# HackadayPin.net
KiCad netlist of a schematic drawn in EAGLE
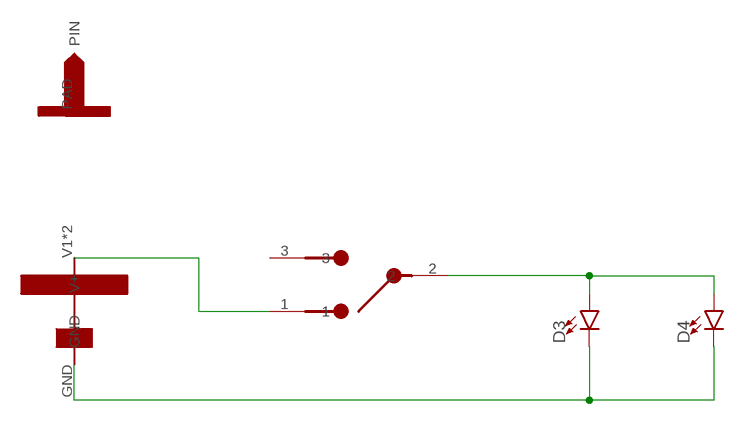
[diagram p0: schematic, sheet 1]

(export (version "E")
  (design (tool "Eeschema 10.0.6"))
  (components
    (comp (ref "D3")
      (value "LED5MM")
      (footprint "eagle-import:LED_5MM")
      (libsource (lib "eagle-import") (part "LED5MM"))
    )
    (comp (ref "D4")
      (value "LED5MM")
      (footprint "eagle-import:LED_5MM")
      (libsource (lib "eagle-import") (part "LED5MM"))
    )
    (comp (ref "U$1")
      (value "1220BATTERY")
      (footprint "eagle-import:BK-916")
      (libsource (lib "eagle-import") (part "1220BATTERY"))
    )
    (comp (ref "U$2")
      (value "ALPSSLIDESW")
      (footprint "eagle-import:SWITCH-SSSS810701")
      (libsource (lib "eagle-import") (part "ALPSSLIDESW"))
    )
    (comp (ref "U$3")
      (value "LAPELPIN")
      (footprint "eagle-import:LAPELPIN")
      (libsource (lib "eagle-import") (part "LAPELPIN"))
    )
  )
  (nets
    (net (code "1") (name "Net-(D3-C)") (class "Default")
      (node (ref "D3") (pin "K") (pinfunction "C_K") (pintype "passive"))
      (node (ref "D4") (pin "K") (pinfunction "C_K") (pintype "passive"))
      (node (ref "U$1") (pin "GND") (pinfunction "GND_GND") (pintype "bidirectional"))
    )
    (net (code "2") (name "Net-(D3-PadA)") (class "Default")
      (node (ref "D3") (pin "A") (pinfunction "A_A") (pintype "passive"))
      (node (ref "D4") (pin "A") (pinfunction "A_A") (pintype "passive"))
      (node (ref "U$2") (pin "2") (pinfunction "2_2") (pintype "bidirectional"))
    )
    (net (code "3") (name "Net-(U$1-V+-PadV1)") (class "Default")
      (node (ref "U$1") (pin "V1") (pinfunction "V+_V1") (pintype "bidirectional"))
      (node (ref "U$1") (pin "V2") (pinfunction "V+_V2") (pintype "bidirectional"))
      (node (ref "U$2") (pin "1") (pinfunction "1_1") (pintype "bidirectional"))
    )
    (net (code "4") (name "unconnected-(U$2-Pad3)") (class "Default")
      (node (ref "U$2") (pin "3") (pinfunction "3_3") (pintype "bidirectional"))
    )
    (net (code "5") (name "unconnected-(U$3-PIN-PadPAD)") (class "Default")
      (node (ref "U$3") (pin "PAD") (pinfunction "PIN_PAD") (pintype "bidirectional"))
    )
  )
)
